# MicroMouse.net
KiCad netlist of a schematic drawn in Altium Designer
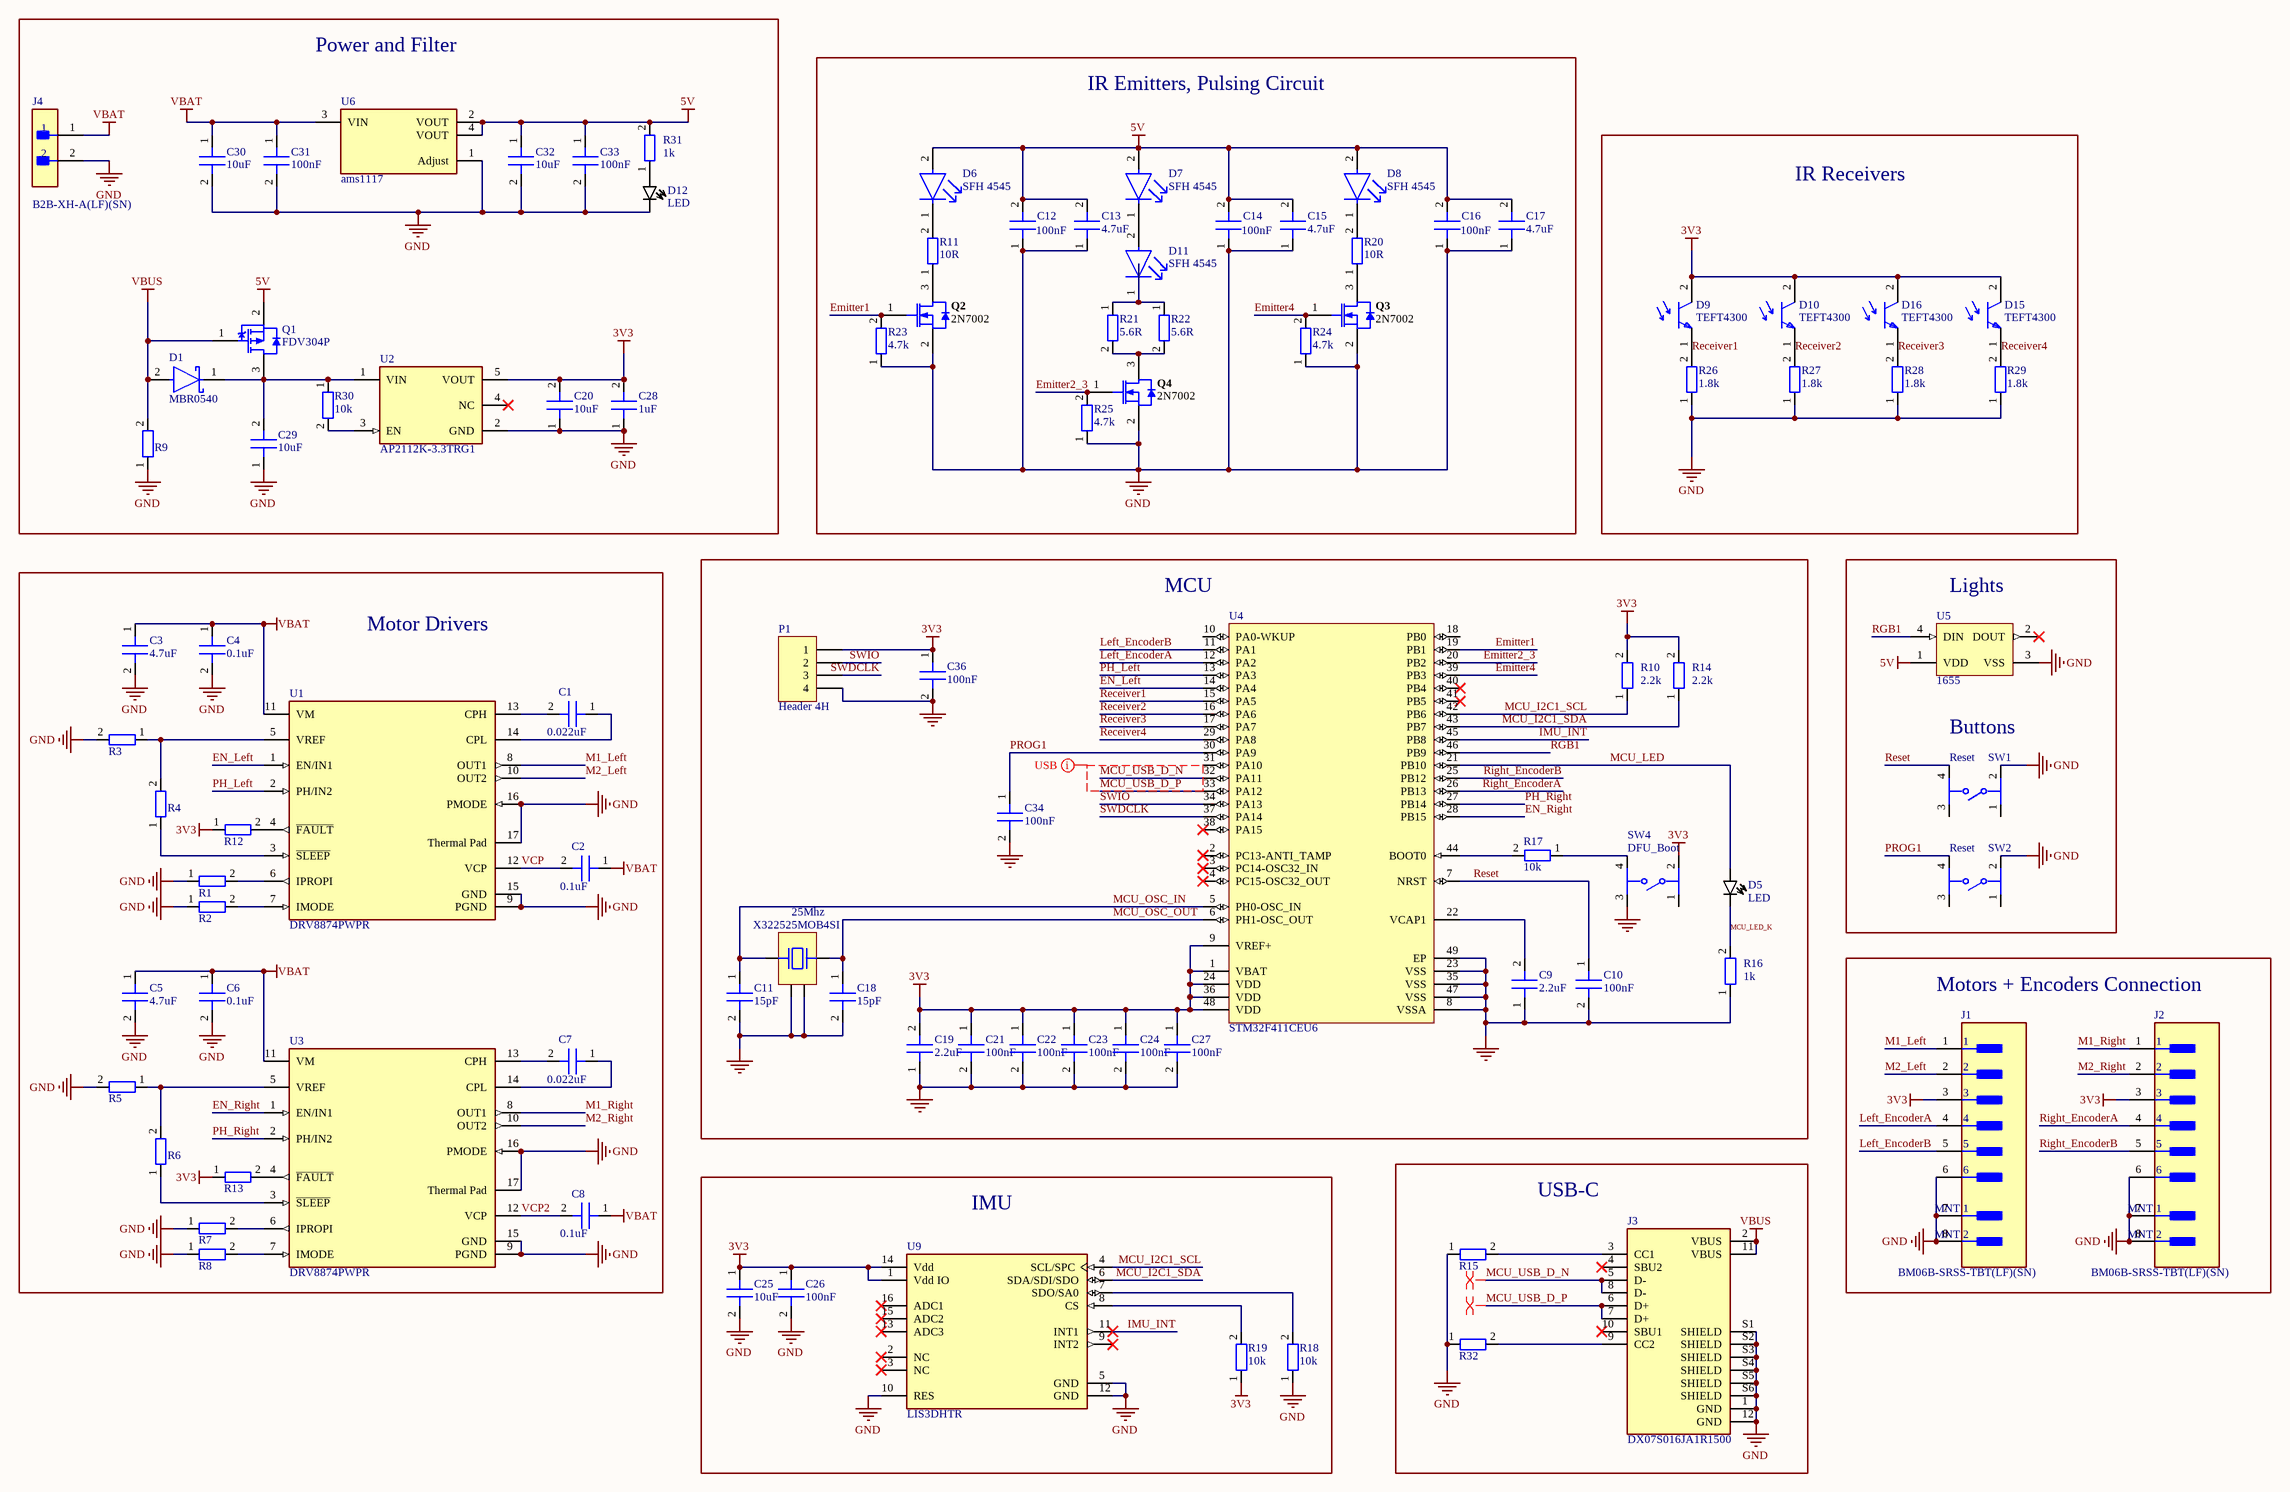
[diagram p0: MicroMouse.SchDoc]

(export (version "E")
  (design (tool "Eeschema 10.0.6"))
  (components
    (comp (ref "C1")
      (value "0.022uF")
      (footprint "IPC C C0603 No Silk")
      (libsource (lib "UBC AeroDesign") (part "CAP 0402 4.7uF CL05A475MP5NRNC"))
    )
    (comp (ref "C2")
      (value "0.1uF")
      (footprint "IPC C C0603 No Silk")
      (description "16V rated")
      (libsource (lib "UBC AeroDesign") (part "CAP 0402 4.7uF CL05A475MP5NRNC"))
    )
    (comp (ref "C3")
      (value "4.7uF")
      (footprint "IPC C C0603 No Silk")
      (libsource (lib "UBC AeroDesign") (part "CAP 0402 4.7uF CL05A475MP5NRNC"))
    )
    (comp (ref "C4")
      (value "0.1uF")
      (footprint "IPC C C0603 No Silk")
      (libsource (lib "UBC AeroDesign") (part "CAP 0402 4.7uF CL05A475MP5NRNC"))
    )
    (comp (ref "C5")
      (value "4.7uF")
      (footprint "IPC C C0603 No Silk")
      (libsource (lib "UBC AeroDesign") (part "CAP 0402 4.7uF CL05A475MP5NRNC"))
    )
    (comp (ref "C6")
      (value "0.1uF")
      (footprint "IPC C C0603 No Silk")
      (libsource (lib "UBC AeroDesign") (part "CAP 0402 4.7uF CL05A475MP5NRNC"))
    )
    (comp (ref "C7")
      (value "0.022uF")
      (footprint "IPC C C0603 No Silk")
      (libsource (lib "UBC AeroDesign") (part "CAP 0402 4.7uF CL05A475MP5NRNC"))
    )
    (comp (ref "C8")
      (value "0.1uF")
      (footprint "IPC C C0603 No Silk")
      (description "16V rated")
      (libsource (lib "UBC AeroDesign") (part "CAP 0402 4.7uF CL05A475MP5NRNC"))
    )
    (comp (ref "C9")
      (value "2.2uF")
      (footprint "IPC C C0603 No Silk")
      (libsource (lib "UBC AeroDesign") (part "CAP 0402 4.7uF CL05A475MP5NRNC"))
    )
    (comp (ref "C10")
      (value "100nF")
      (footprint "IPC C C0603 No Silk")
      (libsource (lib "UBC AeroDesign") (part "CAP 0402 4.7uF CL05A475MP5NRNC"))
    )
    (comp (ref "C11")
      (value "15pF")
      (footprint "IPC C C0603 No Silk")
      (libsource (lib "UBC AeroDesign") (part "CAP 0402 4.7uF CL05A475MP5NRNC"))
    )
    (comp (ref "C12")
      (value "100nF")
      (footprint "IPC C C0603 No Silk")
      (libsource (lib "UBC AeroDesign") (part "CAP 0402 4.7uF CL05A475MP5NRNC"))
    )
    (comp (ref "C13")
      (value "4.7uF")
      (footprint "IPC C C0603 No Silk")
      (libsource (lib "UBC AeroDesign") (part "CAP 0402 4.7uF CL05A475MP5NRNC"))
    )
    (comp (ref "C14")
      (value "100nF")
      (footprint "IPC C C0603 No Silk")
      (libsource (lib "UBC AeroDesign") (part "CAP 0402 4.7uF CL05A475MP5NRNC"))
    )
    (comp (ref "C15")
      (value "4.7uF")
      (footprint "IPC C C0603 No Silk")
      (libsource (lib "UBC AeroDesign") (part "CAP 0402 4.7uF CL05A475MP5NRNC"))
    )
    (comp (ref "C16")
      (value "100nF")
      (footprint "IPC C C0603 No Silk")
      (libsource (lib "UBC AeroDesign") (part "CAP 0402 4.7uF CL05A475MP5NRNC"))
    )
    (comp (ref "C17")
      (value "4.7uF")
      (footprint "IPC C C0603 No Silk")
      (libsource (lib "UBC AeroDesign") (part "CAP 0402 4.7uF CL05A475MP5NRNC"))
    )
    (comp (ref "C18")
      (value "15pF")
      (footprint "IPC C C0603 No Silk")
      (libsource (lib "UBC AeroDesign") (part "CAP 0402 4.7uF CL05A475MP5NRNC"))
    )
    (comp (ref "C19")
      (value "2.2uF")
      (footprint "IPC C C0603 No Silk")
      (libsource (lib "UBC AeroDesign") (part "CAP 0402 4.7uF CL05A475MP5NRNC"))
    )
    (comp (ref "C20")
      (value "10uF")
      (footprint "IPC C C0603 No Silk")
      (libsource (lib "UBC AeroDesign") (part "CAP 0402 4.7uF CL05A475MP5NRNC"))
    )
    (comp (ref "C21")
      (value "100nF")
      (footprint "IPC C C0603 No Silk")
      (libsource (lib "UBC AeroDesign") (part "CAP 0402 4.7uF CL05A475MP5NRNC"))
    )
    (comp (ref "C22")
      (value "100nF")
      (footprint "IPC C C0603 No Silk")
      (libsource (lib "UBC AeroDesign") (part "CAP 0402 4.7uF CL05A475MP5NRNC"))
    )
    (comp (ref "C23")
      (value "100nF")
      (footprint "IPC C C0603 No Silk")
      (libsource (lib "UBC AeroDesign") (part "CAP 0402 4.7uF CL05A475MP5NRNC"))
    )
    (comp (ref "C24")
      (value "100nF")
      (footprint "IPC C C0603 No Silk")
      (libsource (lib "UBC AeroDesign") (part "CAP 0402 4.7uF CL05A475MP5NRNC"))
    )
    (comp (ref "C25")
      (value "10uF")
      (footprint "IPC C C0603 No Silk")
      (libsource (lib "UBC AeroDesign") (part "CAP 0402 4.7uF CL05A475MP5NRNC"))
    )
    (comp (ref "C26")
      (value "100nF")
      (footprint "IPC C C0603 No Silk")
      (libsource (lib "UBC AeroDesign") (part "CAP 0402 4.7uF CL05A475MP5NRNC"))
    )
    (comp (ref "C27")
      (value "100nF")
      (footprint "IPC C C0603 No Silk")
      (libsource (lib "UBC AeroDesign") (part "CAP 0402 4.7uF CL05A475MP5NRNC"))
    )
    (comp (ref "C28")
      (value "1uF")
      (footprint "IPC C C0603 No Silk")
      (libsource (lib "UBC AeroDesign") (part "CAP 0402 4.7uF CL05A475MP5NRNC"))
    )
    (comp (ref "C29")
      (value "10uF")
      (footprint "IPC C C0603 No Silk")
      (libsource (lib "UBC AeroDesign") (part "CAP 0402 4.7uF CL05A475MP5NRNC"))
    )
    (comp (ref "C30")
      (value "10uF")
      (footprint "IPC C C0603 No Silk")
      (libsource (lib "UBC AeroDesign") (part "CAP 0402 4.7uF CL05A475MP5NRNC"))
    )
    (comp (ref "C31")
      (value "100nF")
      (footprint "IPC C C0603 No Silk")
      (libsource (lib "UBC AeroDesign") (part "CAP 0402 4.7uF CL05A475MP5NRNC"))
    )
    (comp (ref "C32")
      (value "10uF")
      (footprint "IPC C C0603 No Silk")
      (libsource (lib "UBC AeroDesign") (part "CAP 0402 4.7uF CL05A475MP5NRNC"))
    )
    (comp (ref "C33")
      (value "100nF")
      (footprint "IPC C C0603 No Silk")
      (libsource (lib "UBC AeroDesign") (part "CAP 0402 4.7uF CL05A475MP5NRNC"))
    )
    (comp (ref "C34")
      (value "100nF")
      (footprint "IPC C C0603 No Silk")
      (libsource (lib "UBC AeroDesign") (part "CAP 0402 4.7uF CL05A475MP5NRNC"))
    )
    (comp (ref "C36")
      (value "100nF")
      (footprint "IPC C C0603 No Silk")
      (libsource (lib "UBC AeroDesign") (part "CAP 0402 4.7uF CL05A475MP5NRNC"))
    )
    (comp (ref "D1")
      (value "MBR0540")
      (footprint "FP-425-04-MFG")
      (description "DIODE SCHOTTKY 40V 500MA SOD123")
      (libsource (lib "Altium Content Vault") (part "1d6ec82d83fb6aee721767c19dac4b9"))
    )
    (comp (ref "D5")
      (value "LED")
      (footprint "LED0603-FD_BLUE")
      (libsource (lib "UBC AeroDesign") (part "Generic LED 0603"))
    )
    (comp (ref "D6")
      (value "SFH 4545")
      (footprint "FP-SFH_4556-MFG")
      (description "EMITTER IR 860NM 100MA RADIAL")
      (fields
        (field (name "OCTOPART") "https://octopart.com/sfh+4556-osram+opto-31094094")
        (field (name "MANUFACTURER PART NUMBER") "SFH 4556")
      )
      (libsource (lib "Altium Content Vault") (part "8706943c75ba83719d021d2fdc84c58"))
    )
    (comp (ref "D7")
      (value "SFH 4545")
      (footprint "FP-SFH_4556-MFG")
      (description "EMITTER IR 860NM 100MA RADIAL")
      (fields
        (field (name "OCTOPART") "https://octopart.com/sfh+4556-osram+opto-31094094")
        (field (name "MANUFACTURER PART NUMBER") "SFH 4556")
      )
      (libsource (lib "Altium Content Vault") (part "8706943c75ba83719d021d2fdc84c58"))
    )
    (comp (ref "D8")
      (value "SFH 4545")
      (footprint "FP-SFH_4556-MFG")
      (description "EMITTER IR 860NM 100MA RADIAL")
      (fields
        (field (name "OCTOPART") "https://octopart.com/sfh+4556-osram+opto-31094094")
        (field (name "MANUFACTURER PART NUMBER") "SFH 4556")
      )
      (libsource (lib "Altium Content Vault") (part "8706943c75ba83719d021d2fdc84c58"))
    )
    (comp (ref "D9")
      (value "TEFT4300")
      (footprint "FP-6_544-5269_01-4-MFG")
      (description "TEFT4300 PHOTOTRANSISTOR 3.0MM WIDE VIEW / Phototransistor IR Chip Silicon 925nm 2-Pin T-1")
      (libsource (lib "Altium Content Vault") (part "fcf5d96e013ede1c9e051256f92411f"))
    )
    (comp (ref "D10")
      (value "TEFT4300")
      (footprint "FP-6_544-5269_01-4-MFG")
      (description "TEFT4300 PHOTOTRANSISTOR 3.0MM WIDE VIEW / Phototransistor IR Chip Silicon 925nm 2-Pin T-1")
      (libsource (lib "Altium Content Vault") (part "fcf5d96e013ede1c9e051256f92411f"))
    )
    (comp (ref "D11")
      (value "SFH 4545")
      (footprint "FP-SFH_4556-MFG")
      (description "EMITTER IR 860NM 100MA RADIAL")
      (fields
        (field (name "OCTOPART") "https://octopart.com/sfh+4556-osram+opto-31094094")
        (field (name "MANUFACTURER PART NUMBER") "SFH 4556")
      )
      (libsource (lib "Altium Content Vault") (part "8706943c75ba83719d021d2fdc84c58"))
    )
    (comp (ref "D12")
      (value "LED")
      (footprint "LED0603-FD_BLUE")
      (libsource (lib "UBC AeroDesign") (part "Generic LED 0603"))
    )
    (comp (ref "D15")
      (value "TEFT4300")
      (footprint "FP-6_544-5269_01-4-MFG")
      (description "TEFT4300 PHOTOTRANSISTOR 3.0MM WIDE VIEW / Phototransistor IR Chip Silicon 925nm 2-Pin T-1")
      (libsource (lib "Altium Content Vault") (part "fcf5d96e013ede1c9e051256f92411f"))
    )
    (comp (ref "D16")
      (value "TEFT4300")
      (footprint "FP-6_544-5269_01-4-MFG")
      (description "TEFT4300 PHOTOTRANSISTOR 3.0MM WIDE VIEW / Phototransistor IR Chip Silicon 925nm 2-Pin T-1")
      (libsource (lib "Altium Content Vault") (part "fcf5d96e013ede1c9e051256f92411f"))
    )
    (comp (ref "J1")
      (value "BM06B-SRSS-TBT(LF)(SN)")
      (footprint "FP-BM06B-SRSS-TBT_LF_SN-MFG")
      (description "CONN HEADER SMD 6POS 1MM")
      (libsource (lib "Altium Content Vault") (part "ed24c53d9ba001d1a2a686240a95171"))
    )
    (comp (ref "J2")
      (value "BM06B-SRSS-TBT(LF)(SN)")
      (footprint "FP-BM06B-SRSS-TBT_LF_SN-MFG")
      (description "CONN HEADER SMD 6POS 1MM")
      (libsource (lib "Altium Content Vault") (part "ed24c53d9ba001d1a2a686240a95171"))
    )
    (comp (ref "J3")
      (value "DX07S016JA1R1500")
      (footprint "JAE_DX07S016JA1R1500")
      (libsource (lib "UBC AeroDesign") (part "DX07S016JA1R1500"))
    )
    (comp (ref "J4")
      (value "B2B-XH-A(LF)(SN)")
      (footprint "FP-B2B-XH-A_LF_SN-MFG")
      (description "CONN HEADER VERT 2POS 2.5MM")
      (libsource (lib "Altium Content Vault") (part "3bc925449376181038e59eaffc5286c"))
    )
    (comp (ref "P1")
      (value "Header 4H")
      (footprint "HDR1X4H")
      (description "Header, 4-Pin, Right Angle")
      (fields (field (name "PUBLISHER") "Altium Limited"))
      (libsource (lib "UBC AeroDesign") (part "Header 4H"))
    )
    (comp (ref "Q1")
      (value "FDV304P")
      (footprint "FAIR-SOT23-3_V")
      (fields (field (name "MANUFACTURER") "FairchildSemiconductor"))
      (libsource (lib "Altium Content Vault") (part "PEMOS-GSD-3_B"))
    )
    (comp (ref "Q2")
      (value "2N7002")
      (footprint "INF-PG-SOT23_M")
      (fields (field (name "MANUFACTURER") "Infineon"))
      (libsource (lib "Altium Content Vault") (part "INF-NDMOS-GSD-3"))
    )
    (comp (ref "Q3")
      (value "2N7002")
      (footprint "INF-PG-SOT23_M")
      (fields (field (name "MANUFACTURER") "Infineon"))
      (libsource (lib "Altium Content Vault") (part "INF-NDMOS-GSD-3"))
    )
    (comp (ref "Q4")
      (value "2N7002")
      (footprint "INF-PG-SOT23_M")
      (fields (field (name "MANUFACTURER") "Infineon"))
      (libsource (lib "Altium Content Vault") (part "INF-NDMOS-GSD-3"))
    )
    (comp (ref "R1")
      (value "2.49k")
      (footprint "IPC C R0603 No Silk")
      (libsource (lib "UBC AeroDesign") (part "RES 0402 5.1k 0402WGF5101TCE"))
    )
    (comp (ref "R2")
      (value "20k")
      (footprint "IPC C R0603 No Silk")
      (libsource (lib "UBC AeroDesign") (part "RES 0402 5.1k 0402WGF5101TCE"))
    )
    (comp (ref "R3")
      (value "0")
      (footprint "IPC C R0603 No Silk")
      (libsource (lib "UBC AeroDesign") (part "RES 0402 5.1k 0402WGF5101TCE"))
    )
    (comp (ref "R4")
      (value "10k")
      (footprint "IPC C R0603 No Silk")
      (libsource (lib "UBC AeroDesign") (part "RES 0402 5.1k 0402WGF5101TCE"))
    )
    (comp (ref "R5")
      (value "0")
      (footprint "IPC C R0603 No Silk")
      (libsource (lib "UBC AeroDesign") (part "RES 0402 5.1k 0402WGF5101TCE"))
    )
    (comp (ref "R6")
      (value "10k")
      (footprint "IPC C R0603 No Silk")
      (libsource (lib "UBC AeroDesign") (part "RES 0402 5.1k 0402WGF5101TCE"))
    )
    (comp (ref "R7")
      (value "2.49k")
      (footprint "IPC C R0603 No Silk")
      (libsource (lib "UBC AeroDesign") (part "RES 0402 5.1k 0402WGF5101TCE"))
    )
    (comp (ref "R8")
      (value "20k")
      (footprint "IPC C R0603 No Silk")
      (libsource (lib "UBC AeroDesign") (part "RES 0402 5.1k 0402WGF5101TCE"))
    )
    (comp (ref "R9")
      (value "100k")
      (footprint "IPC C R0603 No Silk")
      (libsource (lib "UBC AeroDesign") (part "RES 0402 5.1k 0402WGF5101TCE"))
    )
    (comp (ref "R10")
      (value "2.2k")
      (footprint "IPC C R0603 No Silk")
      (libsource (lib "UBC AeroDesign") (part "RES 0402 5.1k 0402WGF5101TCE"))
    )
    (comp (ref "R11")
      (value "10R")
      (footprint "IPC C R0603 No Silk")
      (libsource (lib "UBC AeroDesign") (part "RES 0402 5.1k 0402WGF5101TCE"))
    )
    (comp (ref "R12")
      (value "10k")
      (footprint "IPC C R0603 No Silk")
      (libsource (lib "UBC AeroDesign") (part "RES 0402 5.1k 0402WGF5101TCE"))
    )
    (comp (ref "R13")
      (value "10k")
      (footprint "IPC C R0603 No Silk")
      (libsource (lib "UBC AeroDesign") (part "RES 0402 5.1k 0402WGF5101TCE"))
    )
    (comp (ref "R14")
      (value "2.2k")
      (footprint "IPC C R0603 No Silk")
      (libsource (lib "UBC AeroDesign") (part "RES 0402 5.1k 0402WGF5101TCE"))
    )
    (comp (ref "R15")
      (value "Generic RES 0603")
      (footprint "IPC C R0603 No Silk")
      (libsource (lib "UBC AeroDesign") (part "RES 0402 5.1k 0402WGF5101TCE"))
    )
    (comp (ref "R16")
      (value "1k")
      (footprint "IPC C R0603 No Silk")
      (libsource (lib "UBC AeroDesign") (part "RES 0402 5.1k 0402WGF5101TCE"))
    )
    (comp (ref "R17")
      (value "10k")
      (footprint "IPC C R0603 No Silk")
      (libsource (lib "UBC AeroDesign") (part "RES 0402 5.1k 0402WGF5101TCE"))
    )
    (comp (ref "R18")
      (value "10k")
      (footprint "IPC C R0603 No Silk")
      (libsource (lib "UBC AeroDesign") (part "RES 0402 5.1k 0402WGF5101TCE"))
    )
    (comp (ref "R19")
      (value "10k")
      (footprint "IPC C R0603 No Silk")
      (libsource (lib "UBC AeroDesign") (part "RES 0402 5.1k 0402WGF5101TCE"))
    )
    (comp (ref "R20")
      (value "10R")
      (footprint "IPC C R0603 No Silk")
      (libsource (lib "UBC AeroDesign") (part "RES 0402 5.1k 0402WGF5101TCE"))
    )
    (comp (ref "R21")
      (value "5.6R")
      (footprint "IPC C R0603 No Silk")
      (libsource (lib "UBC AeroDesign") (part "RES 0402 5.1k 0402WGF5101TCE"))
    )
    (comp (ref "R22")
      (value "5.6R")
      (footprint "IPC C R0603 No Silk")
      (libsource (lib "UBC AeroDesign") (part "RES 0402 5.1k 0402WGF5101TCE"))
    )
    (comp (ref "R23")
      (value "4.7k")
      (footprint "IPC C R0603 No Silk")
      (libsource (lib "UBC AeroDesign") (part "RES 0402 5.1k 0402WGF5101TCE"))
    )
    (comp (ref "R24")
      (value "4.7k")
      (footprint "IPC C R0603 No Silk")
      (libsource (lib "UBC AeroDesign") (part "RES 0402 5.1k 0402WGF5101TCE"))
    )
    (comp (ref "R25")
      (value "4.7k")
      (footprint "IPC C R0603 No Silk")
      (libsource (lib "UBC AeroDesign") (part "RES 0402 5.1k 0402WGF5101TCE"))
    )
    (comp (ref "R26")
      (value "1.8k")
      (footprint "IPC C R0603 No Silk")
      (libsource (lib "UBC AeroDesign") (part "RES 0402 5.1k 0402WGF5101TCE"))
    )
    (comp (ref "R27")
      (value "1.8k")
      (footprint "IPC C R0603 No Silk")
      (libsource (lib "UBC AeroDesign") (part "RES 0402 5.1k 0402WGF5101TCE"))
    )
    (comp (ref "R28")
      (value "1.8k")
      (footprint "IPC C R0603 No Silk")
      (libsource (lib "UBC AeroDesign") (part "RES 0402 5.1k 0402WGF5101TCE"))
    )
    (comp (ref "R29")
      (value "1.8k")
      (footprint "IPC C R0603 No Silk")
      (libsource (lib "UBC AeroDesign") (part "RES 0402 5.1k 0402WGF5101TCE"))
    )
    (comp (ref "R30")
      (value "10k")
      (footprint "IPC C R0603 No Silk")
      (libsource (lib "UBC AeroDesign") (part "RES 0402 5.1k 0402WGF5101TCE"))
    )
    (comp (ref "R31")
      (value "1k")
      (footprint "IPC C R0603 No Silk")
      (libsource (lib "UBC AeroDesign") (part "RES 0402 5.1k 0402WGF5101TCE"))
    )
    (comp (ref "R32")
      (value "Generic RES 0603")
      (footprint "IPC C R0603 No Silk")
      (libsource (lib "UBC AeroDesign") (part "RES 0402 5.1k 0402WGF5101TCE"))
    )
    (comp (ref "SW1")
      (value "Reset")
      (footprint "FP-PTS526SK15SMTR2LFS-MFG")
      (description "TACT 5.2 X 5.2, 1.5 MM H, 260GF,")
      (fields
        (field (name "MANUFACTURER") "C&K")
        (field (name "MANUFACTURER PART NUMBER") "PTS526SK15SMTR2LFS")
      )
      (libsource (lib "Altium Content Vault") (part "b8895f3f4cefb76e1819d2863dba89b"))
    )
    (comp (ref "SW2")
      (value "Reset")
      (footprint "FP-PTS526SK15SMTR2LFS-MFG")
      (description "TACT 5.2 X 5.2, 1.5 MM H, 260GF,")
      (fields
        (field (name "MANUFACTURER") "C&K")
        (field (name "MANUFACTURER PART NUMBER") "PTS526SK15SMTR2LFS")
      )
      (libsource (lib "Altium Content Vault") (part "b8895f3f4cefb76e1819d2863dba89b"))
    )
    (comp (ref "SW4")
      (value "DFU_Boot")
      (footprint "FP-PTS526SK15SMTR2LFS-MFG")
      (description "TACT 5.2 X 5.2, 1.5 MM H, 260GF,")
      (fields
        (field (name "MANUFACTURER") "C&K")
        (field (name "MANUFACTURER PART NUMBER") "PTS526SK15SMTR2LFS")
      )
      (libsource (lib "Altium Content Vault") (part "b8895f3f4cefb76e1819d2863dba89b"))
    )
    (comp (ref "U1")
      (value "DRV8874PWPR")
      (footprint "FP-PWP0016J-MFG")
      (description "DRV8874 H-BRIDGE MOTOR DRIVER")
      (libsource (lib "Altium Content Vault") (part "a5fc859173bb0b9b9cdb17a7cc0dfbc"))
    )
    (comp (ref "U2")
      (value "AP2112K-3.3TRG1")
      (footprint "FP-SOT25-IPC_A")
      (description "IC REG LINEAR 3.3V 600MA SOT25")
      (libsource (lib "Altium Content Vault") (part "c8ab751aee5229183125ab046a11caa"))
    )
    (comp (ref "U3")
      (value "DRV8874PWPR")
      (footprint "FP-PWP0016J-MFG")
      (description "DRV8874 H-BRIDGE MOTOR DRIVER")
      (libsource (lib "Altium Content Vault") (part "a5fc859173bb0b9b9cdb17a7cc0dfbc"))
    )
    (comp (ref "U4")
      (value "STM32F411CEU6")
      (footprint "STM-UFQFPN48_L")
      (libsource (lib "Altium Content Vault") (part "MC-ARM-STM32F411-UFQFPN48"))
    )
    (comp (ref "U5")
      (value "1655")
      (footprint "ADA-RGB-1655_V")
      (fields (field (name "MANUFACTURER") "Adafruit-Industries-LLC"))
      (libsource (lib "Altium Content Vault") (part "ADA-RGB-1655-4"))
    )
    (comp (ref "U6")
      (value "ams1117")
      (footprint "FP-ams1117-IPC_C")
      (description "1A LOW DROPOUT VOLTAGE REGULATOR")
      (libsource (lib "Altium Content Vault") (part "59ad430b93a2c51b3e6ee7c3b069677"))
    )
    (comp (ref "U9")
      (value "LIS3DHTR")
      (footprint "FP-LGA-16-7983231-MFG")
      (description "ACCEL 2-16G I2C/SPI 16LGA")
      (libsource (lib "Altium Content Vault") (part "1e4772b22d749da4b53766bc623c8dd"))
    )
    (comp (ref "X322525MOB4SI")
      (value "25Mhz")
      (footprint "OSC-SMD_4P-L3.2-W2.5-BL")
      (fields (field (name "MANUFACTURER") "YXC(扬兴晶振)") (field (name "MANUFACTURER PART") "X322525MOB4SI"))
      (libsource (lib "JLCPCB Library") (part "Crystal 25MHz X322525MOB4SI"))
    )
  )
  (nets
    (net (code "1") (name "/EN_Left") (class "Default")
      (node (ref "U1") (pin "1") (pinfunction "EN/IN1_1") (pintype "input"))
      (node (ref "U4") (pin "14") (pinfunction "PA4_14") (pintype "bidirectional"))
    )
    (net (code "2") (name "/EN_Right") (class "Default")
      (node (ref "U3") (pin "1") (pinfunction "EN/IN1_1") (pintype "input"))
      (node (ref "U4") (pin "28") (pinfunction "PB15_28") (pintype "bidirectional"))
    )
    (net (code "3") (name "/Emitter1") (class "Default")
      (node (ref "Q2") (pin "1") (pinfunction "GATE_1") (pintype "passive"))
      (node (ref "R23") (pin "2") (pinfunction "2_2") (pintype "passive"))
      (node (ref "U4") (pin "19") (pinfunction "PB1_19") (pintype "bidirectional"))
    )
    (net (code "4") (name "/Emitter2_3") (class "Default")
      (node (ref "Q4") (pin "1") (pinfunction "GATE_1") (pintype "passive"))
      (node (ref "R25") (pin "2") (pinfunction "2_2") (pintype "passive"))
      (node (ref "U4") (pin "20") (pinfunction "PB2_20") (pintype "bidirectional"))
    )
    (net (code "5") (name "/Emitter4") (class "Default")
      (node (ref "Q3") (pin "1") (pinfunction "GATE_1") (pintype "passive"))
      (node (ref "R24") (pin "2") (pinfunction "2_2") (pintype "passive"))
      (node (ref "U4") (pin "39") (pinfunction "PB3_39") (pintype "bidirectional"))
    )
    (net (code "6") (name "/IMU_INT") (class "Default")
      (node (ref "U4") (pin "45") (pinfunction "PB8_45") (pintype "bidirectional"))
      (node (ref "U9") (pin "11") (pinfunction "INT1_11") (pintype "output"))
    )
    (net (code "7") (name "/Left_EncoderA") (class "Default")
      (node (ref "J1") (pin "4") (pinfunction "4_4") (pintype "passive"))
      (node (ref "U4") (pin "12") (pinfunction "PA2_12") (pintype "bidirectional"))
    )
    (net (code "8") (name "/Left_EncoderB") (class "Default")
      (node (ref "J1") (pin "5") (pinfunction "5_5") (pintype "passive"))
      (node (ref "U4") (pin "11") (pinfunction "PA1_11") (pintype "bidirectional"))
    )
    (net (code "9") (name "/M1_Left") (class "Default")
      (node (ref "J1") (pin "1") (pinfunction "1_1") (pintype "passive"))
      (node (ref "U1") (pin "8") (pinfunction "OUT1_8") (pintype "output"))
    )
    (net (code "10") (name "/M1_Right") (class "Default")
      (node (ref "J2") (pin "1") (pinfunction "1_1") (pintype "passive"))
      (node (ref "U3") (pin "8") (pinfunction "OUT1_8") (pintype "output"))
    )
    (net (code "11") (name "/M2_Left") (class "Default")
      (node (ref "J1") (pin "2") (pinfunction "2_2") (pintype "passive"))
      (node (ref "U1") (pin "10") (pinfunction "OUT2_10") (pintype "output"))
    )
    (net (code "12") (name "/M2_Right") (class "Default")
      (node (ref "J2") (pin "2") (pinfunction "2_2") (pintype "passive"))
      (node (ref "U3") (pin "10") (pinfunction "OUT2_10") (pintype "output"))
    )
    (net (code "13") (name "/MCU_I2C1_SCL") (class "Default")
      (node (ref "R10") (pin "1") (pinfunction "1_1") (pintype "passive"))
      (node (ref "U4") (pin "42") (pinfunction "PB6_42") (pintype "bidirectional"))
      (node (ref "U9") (pin "4") (pinfunction "SCL/SPC_4") (pintype "input"))
    )
    (net (code "14") (name "/MCU_I2C1_SDA") (class "Default")
      (node (ref "R14") (pin "1") (pinfunction "1_1") (pintype "passive"))
      (node (ref "U4") (pin "43") (pinfunction "PB7_43") (pintype "bidirectional"))
      (node (ref "U9") (pin "6") (pinfunction "SDA/SDI/SDO_6") (pintype "bidirectional"))
    )
    (net (code "15") (name "/MCU_LED") (class "Default")
      (node (ref "D5") (pin "1") (pinfunction "A_1") (pintype "passive"))
      (node (ref "U4") (pin "21") (pinfunction "PB10_21") (pintype "bidirectional"))
    )
    (net (code "16") (name "/MCU_LED_K") (class "Default")
      (node (ref "D5") (pin "2") (pinfunction "C_2") (pintype "passive"))
      (node (ref "R16") (pin "2") (pinfunction "2_2") (pintype "passive"))
    )
    (net (code "17") (name "/MCU_OSC_IN") (class "Default")
      (node (ref "C11") (pin "1") (pinfunction "1_1") (pintype "passive"))
      (node (ref "U4") (pin "5") (pinfunction "PH0-OSC_IN_5") (pintype "bidirectional"))
      (node (ref "X322525MOB4SI") (pin "1") (pinfunction "1_1") (pintype "passive"))
    )
    (net (code "18") (name "/MCU_OSC_OUT") (class "Default")
      (node (ref "C18") (pin "1") (pinfunction "1_1") (pintype "passive"))
      (node (ref "U4") (pin "6") (pinfunction "PH1-OSC_OUT_6") (pintype "bidirectional"))
      (node (ref "X322525MOB4SI") (pin "3") (pinfunction "3_3") (pintype "passive"))
    )
    (net (code "19") (name "/MCU_USB_D_N") (class "Default")
      (node (ref "J3") (pin "5") (pinfunction "D-_5") (pintype "passive"))
      (node (ref "J3") (pin "8") (pinfunction "D-_8") (pintype "passive"))
      (node (ref "U4") (pin "32") (pinfunction "PA11_32") (pintype "bidirectional"))
    )
    (net (code "20") (name "/MCU_USB_D_P") (class "Default")
      (node (ref "J3") (pin "6") (pinfunction "D+_6") (pintype "passive"))
      (node (ref "J3") (pin "7") (pinfunction "D+_7") (pintype "passive"))
      (node (ref "U4") (pin "33") (pinfunction "PA12_33") (pintype "bidirectional"))
    )
    (net (code "21") (name "/PH_Left") (class "Default")
      (node (ref "U1") (pin "2") (pinfunction "PH/IN2_2") (pintype "input"))
      (node (ref "U4") (pin "13") (pinfunction "PA3_13") (pintype "bidirectional"))
    )
    (net (code "22") (name "/PH_Right") (class "Default")
      (node (ref "U3") (pin "2") (pinfunction "PH/IN2_2") (pintype "input"))
      (node (ref "U4") (pin "27") (pinfunction "PB14_27") (pintype "bidirectional"))
    )
    (net (code "23") (name "/PROG1") (class "Default")
      (node (ref "C34") (pin "1") (pinfunction "1_1") (pintype "passive"))
      (node (ref "SW2") (pin "4") (pinfunction "4_4") (pintype "passive"))
      (node (ref "U4") (pin "30") (pinfunction "PA9_30") (pintype "bidirectional"))
    )
    (net (code "24") (name "/RGB1") (class "Default")
      (node (ref "U4") (pin "46") (pinfunction "PB9_46") (pintype "bidirectional"))
      (node (ref "U5") (pin "4") (pinfunction "DIN_4") (pintype "input"))
    )
    (net (code "25") (name "/Receiver1") (class "Default")
      (node (ref "D9") (pin "1") (pinfunction "E_1") (pintype "passive"))
      (node (ref "R26") (pin "2") (pinfunction "2_2") (pintype "passive"))
      (node (ref "U4") (pin "15") (pinfunction "PA5_15") (pintype "bidirectional"))
    )
    (net (code "26") (name "/Receiver2") (class "Default")
      (node (ref "D10") (pin "1") (pinfunction "E_1") (pintype "passive"))
      (node (ref "R27") (pin "2") (pinfunction "2_2") (pintype "passive"))
      (node (ref "U4") (pin "16") (pinfunction "PA6_16") (pintype "bidirectional"))
    )
    (net (code "27") (name "/Receiver3") (class "Default")
      (node (ref "D16") (pin "1") (pinfunction "E_1") (pintype "passive"))
      (node (ref "R28") (pin "2") (pinfunction "2_2") (pintype "passive"))
      (node (ref "U4") (pin "17") (pinfunction "PA7_17") (pintype "bidirectional"))
    )
    (net (code "28") (name "/Receiver4") (class "Default")
      (node (ref "D15") (pin "1") (pinfunction "E_1") (pintype "passive"))
      (node (ref "R29") (pin "2") (pinfunction "2_2") (pintype "passive"))
      (node (ref "U4") (pin "29") (pinfunction "PA8_29") (pintype "bidirectional"))
    )
    (net (code "29") (name "/Reset") (class "Default")
      (node (ref "C10") (pin "1") (pinfunction "1_1") (pintype "passive"))
      (node (ref "SW1") (pin "4") (pinfunction "4_4") (pintype "passive"))
      (node (ref "U4") (pin "7") (pinfunction "NRST_7") (pintype "bidirectional"))
    )
    (net (code "30") (name "/Right_EncoderA") (class "Default")
      (node (ref "J2") (pin "4") (pinfunction "4_4") (pintype "passive"))
      (node (ref "U4") (pin "26") (pinfunction "PB13_26") (pintype "bidirectional"))
    )
    (net (code "31") (name "/Right_EncoderB") (class "Default")
      (node (ref "J2") (pin "5") (pinfunction "5_5") (pintype "passive"))
      (node (ref "U4") (pin "25") (pinfunction "PB12_25") (pintype "bidirectional"))
    )
    (net (code "32") (name "/SWDCLK") (class "Default")
      (node (ref "P1") (pin "3") (pinfunction "3_3") (pintype "passive"))
      (node (ref "U4") (pin "37") (pinfunction "PA14_37") (pintype "bidirectional"))
    )
    (net (code "33") (name "/SWIO") (class "Default")
      (node (ref "P1") (pin "2") (pinfunction "2_2") (pintype "passive"))
      (node (ref "U4") (pin "34") (pinfunction "PA13_34") (pintype "bidirectional"))
    )
    (net (code "34") (name "/VCP") (class "Default")
      (node (ref "C2") (pin "2") (pinfunction "2_2") (pintype "passive"))
      (node (ref "U1") (pin "12") (pinfunction "VCP_12") (pintype "power_in"))
    )
    (net (code "35") (name "/VCP2") (class "Default")
      (node (ref "C8") (pin "2") (pinfunction "2_2") (pintype "passive"))
      (node (ref "U3") (pin "12") (pinfunction "VCP_12") (pintype "power_in"))
    )
    (net (code "36") (name "3V3") (class "Default")
      (node (ref "C19") (pin "2") (pinfunction "2_2") (pintype "passive"))
      (node (ref "C20") (pin "2") (pinfunction "2_2") (pintype "passive"))
      (node (ref "C21") (pin "1") (pinfunction "1_1") (pintype "passive"))
      (node (ref "C22") (pin "1") (pinfunction "1_1") (pintype "passive"))
      (node (ref "C23") (pin "1") (pinfunction "1_1") (pintype "passive"))
      (node (ref "C24") (pin "1") (pinfunction "1_1") (pintype "passive"))
      (node (ref "C25") (pin "1") (pinfunction "1_1") (pintype "passive"))
      (node (ref "C26") (pin "1") (pinfunction "1_1") (pintype "passive"))
      (node (ref "C27") (pin "1") (pinfunction "1_1") (pintype "passive"))
      (node (ref "C28") (pin "2") (pinfunction "2_2") (pintype "passive"))
      (node (ref "C36") (pin "1") (pinfunction "1_1") (pintype "passive"))
      (node (ref "D10") (pin "2") (pinfunction "C_2") (pintype "passive"))
      (node (ref "D15") (pin "2") (pinfunction "C_2") (pintype "passive"))
      (node (ref "D16") (pin "2") (pinfunction "C_2") (pintype "passive"))
      (node (ref "D9") (pin "2") (pinfunction "C_2") (pintype "passive"))
      (node (ref "J1") (pin "3") (pinfunction "3_3") (pintype "passive"))
      (node (ref "J2") (pin "3") (pinfunction "3_3") (pintype "passive"))
      (node (ref "P1") (pin "1") (pinfunction "1_1") (pintype "passive"))
      (node (ref "R10") (pin "2") (pinfunction "2_2") (pintype "passive"))
      (node (ref "R12") (pin "1") (pinfunction "1_1") (pintype "passive"))
      (node (ref "R13") (pin "1") (pinfunction "1_1") (pintype "passive"))
      (node (ref "R14") (pin "2") (pinfunction "2_2") (pintype "passive"))
      (node (ref "R19") (pin "1") (pinfunction "1_1") (pintype "passive"))
      (node (ref "SW4") (pin "2") (pinfunction "2_2") (pintype "passive"))
      (node (ref "U2") (pin "5") (pinfunction "VOUT_5") (pintype "power_in"))
      (node (ref "U4") (pin "1") (pinfunction "VBAT_1") (pintype "power_in"))
      (node (ref "U4") (pin "24") (pinfunction "VDD_24") (pintype "power_in"))
      (node (ref "U4") (pin "36") (pinfunction "VDD_36") (pintype "power_in"))
      (node (ref "U4") (pin "48") (pinfunction "VDD_48") (pintype "power_in"))
      (node (ref "U4") (pin "9") (pinfunction "VREF+_9") (pintype "power_in"))
      (node (ref "U9") (pin "1") (pinfunction "Vdd_IO_1") (pintype "power_in"))
      (node (ref "U9") (pin "14") (pinfunction "Vdd_14") (pintype "power_in"))
    )
    (net (code "37") (name "5V") (class "Default")
      (node (ref "C12") (pin "2") (pinfunction "2_2") (pintype "passive"))
      (node (ref "C13") (pin "2") (pinfunction "2_2") (pintype "passive"))
      (node (ref "C14") (pin "2") (pinfunction "2_2") (pintype "passive"))
      (node (ref "C15") (pin "2") (pinfunction "2_2") (pintype "passive"))
      (node (ref "C16") (pin "2") (pinfunction "2_2") (pintype "passive"))
      (node (ref "C17") (pin "2") (pinfunction "2_2") (pintype "passive"))
      (node (ref "C32") (pin "1") (pinfunction "1_1") (pintype "passive"))
      (node (ref "C33") (pin "1") (pinfunction "1_1") (pintype "passive"))
      (node (ref "D6") (pin "2") (pinfunction "A_2") (pintype "passive"))
      (node (ref "D7") (pin "2") (pinfunction "A_2") (pintype "passive"))
      (node (ref "D8") (pin "2") (pinfunction "A_2") (pintype "passive"))
      (node (ref "Q1") (pin "2") (pinfunction "S_2") (pintype "passive"))
      (node (ref "R31") (pin "2") (pinfunction "2_2") (pintype "passive"))
      (node (ref "U5") (pin "1") (pinfunction "VDD_1") (pintype "power_in"))
      (node (ref "U6") (pin "2") (pinfunction "VOUT_2") (pintype "passive"))
      (node (ref "U6") (pin "4") (pinfunction "VOUT_4") (pintype "passive"))
    )
    (net (code "38") (name "GND") (class "Default")
      (node (ref "C10") (pin "2") (pinfunction "2_2") (pintype "passive"))
      (node (ref "C11") (pin "2") (pinfunction "2_2") (pintype "passive"))
      (node (ref "C12") (pin "1") (pinfunction "1_1") (pintype "passive"))
      (node (ref "C13") (pin "1") (pinfunction "1_1") (pintype "passive"))
      (node (ref "C14") (pin "1") (pinfunction "1_1") (pintype "passive"))
      (node (ref "C15") (pin "1") (pinfunction "1_1") (pintype "passive"))
      (node (ref "C16") (pin "1") (pinfunction "1_1") (pintype "passive"))
      (node (ref "C17") (pin "1") (pinfunction "1_1") (pintype "passive"))
      (node (ref "C18") (pin "2") (pinfunction "2_2") (pintype "passive"))
      (node (ref "C19") (pin "1") (pinfunction "1_1") (pintype "passive"))
      (node (ref "C20") (pin "1") (pinfunction "1_1") (pintype "passive"))
      (node (ref "C21") (pin "2") (pinfunction "2_2") (pintype "passive"))
      (node (ref "C22") (pin "2") (pinfunction "2_2") (pintype "passive"))
      (node (ref "C23") (pin "2") (pinfunction "2_2") (pintype "passive"))
      (node (ref "C24") (pin "2") (pinfunction "2_2") (pintype "passive"))
      (node (ref "C25") (pin "2") (pinfunction "2_2") (pintype "passive"))
      (node (ref "C26") (pin "2") (pinfunction "2_2") (pintype "passive"))
      (node (ref "C27") (pin "2") (pinfunction "2_2") (pintype "passive"))
      (node (ref "C28") (pin "1") (pinfunction "1_1") (pintype "passive"))
      (node (ref "C29") (pin "1") (pinfunction "1_1") (pintype "passive"))
      (node (ref "C3") (pin "2") (pinfunction "2_2") (pintype "passive"))
      (node (ref "C30") (pin "2") (pinfunction "2_2") (pintype "passive"))
      (node (ref "C31") (pin "2") (pinfunction "2_2") (pintype "passive"))
      (node (ref "C32") (pin "2") (pinfunction "2_2") (pintype "passive"))
      (node (ref "C33") (pin "2") (pinfunction "2_2") (pintype "passive"))
      (node (ref "C34") (pin "2") (pinfunction "2_2") (pintype "passive"))
      (node (ref "C36") (pin "2") (pinfunction "2_2") (pintype "passive"))
      (node (ref "C4") (pin "2") (pinfunction "2_2") (pintype "passive"))
      (node (ref "C5") (pin "2") (pinfunction "2_2") (pintype "passive"))
      (node (ref "C6") (pin "2") (pinfunction "2_2") (pintype "passive"))
      (node (ref "C9") (pin "1") (pinfunction "1_1") (pintype "passive"))
      (node (ref "D12") (pin "2") (pinfunction "C_2") (pintype "passive"))
      (node (ref "J1") (pin "6") (pinfunction "6_6") (pintype "passive"))
      (node (ref "J1") (pin "7") (pinfunction "MNT_1_7") (pintype "passive"))
      (node (ref "J1") (pin "8") (pinfunction "MNT_2_8") (pintype "passive"))
      (node (ref "J2") (pin "6") (pinfunction "6_6") (pintype "passive"))
      (node (ref "J2") (pin "7") (pinfunction "MNT_1_7") (pintype "passive"))
      (node (ref "J2") (pin "8") (pinfunction "MNT_2_8") (pintype "passive"))
      (node (ref "J3") (pin "1") (pinfunction "GND_1") (pintype "power_in"))
      (node (ref "J3") (pin "12") (pinfunction "GND_12") (pintype "power_in"))
      (node (ref "J3") (pin "S1") (pinfunction "SHIELD_S1") (pintype "passive"))
      (node (ref "J3") (pin "S2") (pinfunction "SHIELD_S2") (pintype "passive"))
      (node (ref "J3") (pin "S3") (pinfunction "SHIELD_S3") (pintype "passive"))
      (node (ref "J3") (pin "S4") (pinfunction "SHIELD_S4") (pintype "passive"))
      (node (ref "J3") (pin "S5") (pinfunction "SHIELD_S5") (pintype "passive"))
      (node (ref "J3") (pin "S6") (pinfunction "SHIELD_S6") (pintype "passive"))
      (node (ref "J4") (pin "2") (pinfunction "2_2") (pintype "passive"))
      (node (ref "P1") (pin "4") (pinfunction "4_4") (pintype "passive"))
      (node (ref "Q2") (pin "2") (pinfunction "SOURCE_2") (pintype "passive"))
      (node (ref "Q3") (pin "2") (pinfunction "SOURCE_2") (pintype "passive"))
      (node (ref "Q4") (pin "2") (pinfunction "SOURCE_2") (pintype "passive"))
      (node (ref "R1") (pin "1") (pinfunction "1_1") (pintype "passive"))
      (node (ref "R15") (pin "1") (pinfunction "1_1") (pintype "passive"))
      (node (ref "R16") (pin "1") (pinfunction "1_1") (pintype "passive"))
      (node (ref "R18") (pin "1") (pinfunction "1_1") (pintype "passive"))
      (node (ref "R2") (pin "1") (pinfunction "1_1") (pintype "passive"))
      (node (ref "R23") (pin "1") (pinfunction "1_1") (pintype "passive"))
      (node (ref "R24") (pin "1") (pinfunction "1_1") (pintype "passive"))
      (node (ref "R25") (pin "1") (pinfunction "1_1") (pintype "passive"))
      (node (ref "R26") (pin "1") (pinfunction "1_1") (pintype "passive"))
      (node (ref "R27") (pin "1") (pinfunction "1_1") (pintype "passive"))
      (node (ref "R28") (pin "1") (pinfunction "1_1") (pintype "passive"))
      (node (ref "R29") (pin "1") (pinfunction "1_1") (pintype "passive"))
      (node (ref "R3") (pin "2") (pinfunction "2_2") (pintype "passive"))
      (node (ref "R32") (pin "1") (pinfunction "1_1") (pintype "passive"))
      (node (ref "R5") (pin "2") (pinfunction "2_2") (pintype "passive"))
      (node (ref "R7") (pin "1") (pinfunction "1_1") (pintype "passive"))
      (node (ref "R8") (pin "1") (pinfunction "1_1") (pintype "passive"))
      (node (ref "R9") (pin "1") (pinfunction "1_1") (pintype "passive"))
      (node (ref "SW1") (pin "2") (pinfunction "2_2") (pintype "passive"))
      (node (ref "SW2") (pin "2") (pinfunction "2_2") (pintype "passive"))
      (node (ref "SW4") (pin "3") (pinfunction "3_3") (pintype "passive"))
      (node (ref "U1") (pin "15") (pinfunction "GND_15") (pintype "power_in"))
      (node (ref "U1") (pin "16") (pinfunction "PMODE_16") (pintype "input"))
      (node (ref "U1") (pin "17") (pinfunction "Thermal_Pad_17") (pintype "power_in"))
      (node (ref "U1") (pin "9") (pinfunction "PGND_9") (pintype "power_in"))
      (node (ref "U2") (pin "2") (pinfunction "GND_2") (pintype "power_in"))
      (node (ref "U3") (pin "15") (pinfunction "GND_15") (pintype "power_in"))
      (node (ref "U3") (pin "16") (pinfunction "PMODE_16") (pintype "input"))
      (node (ref "U3") (pin "17") (pinfunction "Thermal_Pad_17") (pintype "power_in"))
      (node (ref "U3") (pin "9") (pinfunction "PGND_9") (pintype "power_in"))
      (node (ref "U4") (pin "23") (pinfunction "VSS_23") (pintype "power_in"))
      (node (ref "U4") (pin "35") (pinfunction "VSS_35") (pintype "power_in"))
      (node (ref "U4") (pin "47") (pinfunction "VSS_47") (pintype "power_in"))
      (node (ref "U4") (pin "49") (pinfunction "EP_49") (pintype "power_in"))
      (node (ref "U4") (pin "8") (pinfunction "VSSA_8") (pintype "power_in"))
      (node (ref "U5") (pin "3") (pinfunction "VSS_3") (pintype "power_in"))
      (node (ref "U6") (pin "1") (pinfunction "Adjust_1") (pintype "passive"))
      (node (ref "U9") (pin "10") (pinfunction "RES_10") (pintype "passive"))
      (node (ref "U9") (pin "12") (pinfunction "GND_12") (pintype "power_in"))
      (node (ref "U9") (pin "5") (pinfunction "GND_5") (pintype "power_in"))
      (node (ref "X322525MOB4SI") (pin "2") (pinfunction "2_2") (pintype "passive"))
      (node (ref "X322525MOB4SI") (pin "4") (pinfunction "4_4") (pintype "passive"))
    )
    (net (code "39") (name "Net-(D1-C)") (class "Default")
      (node (ref "C29") (pin "2") (pinfunction "2_2") (pintype "passive"))
      (node (ref "D1") (pin "1") (pinfunction "C_1") (pintype "passive"))
      (node (ref "Q1") (pin "3") (pinfunction "D_3") (pintype "passive"))
      (node (ref "R30") (pin "1") (pinfunction "1_1") (pintype "passive"))
      (node (ref "U2") (pin "1") (pinfunction "VIN_1") (pintype "power_in"))
    )
    (net (code "40") (name "Net-(D6-C)") (class "Default")
      (node (ref "D6") (pin "1") (pinfunction "C_1") (pintype "passive"))
      (node (ref "R11") (pin "2") (pinfunction "2_2") (pintype "passive"))
    )
    (net (code "41") (name "Net-(D8-C)") (class "Default")
      (node (ref "D8") (pin "1") (pinfunction "C_1") (pintype "passive"))
      (node (ref "R20") (pin "2") (pinfunction "2_2") (pintype "passive"))
    )
    (net (code "42") (name "Net-(D11-A)") (class "Default")
      (node (ref "D11") (pin "2") (pinfunction "A_2") (pintype "passive"))
      (node (ref "D7") (pin "1") (pinfunction "C_1") (pintype "passive"))
    )
    (net (code "43") (name "Net-(D11-C)") (class "Default")
      (node (ref "D11") (pin "1") (pinfunction "C_1") (pintype "passive"))
      (node (ref "R21") (pin "1") (pinfunction "1_1") (pintype "passive"))
      (node (ref "R22") (pin "1") (pinfunction "1_1") (pintype "passive"))
    )
    (net (code "44") (name "Net-(D12-A)") (class "Default")
      (node (ref "D12") (pin "1") (pinfunction "A_1") (pintype "passive"))
      (node (ref "R31") (pin "1") (pinfunction "1_1") (pintype "passive"))
    )
    (net (code "45") (name "Net-(J3-CC1)") (class "Default")
      (node (ref "J3") (pin "3") (pinfunction "CC1_3") (pintype "passive"))
      (node (ref "R15") (pin "2") (pinfunction "2_2") (pintype "passive"))
    )
    (net (code "46") (name "Net-(J3-CC2)") (class "Default")
      (node (ref "J3") (pin "9") (pinfunction "CC2_9") (pintype "passive"))
      (node (ref "R32") (pin "2") (pinfunction "2_2") (pintype "passive"))
    )
    (net (code "47") (name "Net-(Q2-DRAIN)") (class "Default")
      (node (ref "Q2") (pin "3") (pinfunction "DRAIN_3") (pintype "passive"))
      (node (ref "R11") (pin "1") (pinfunction "1_1") (pintype "passive"))
    )
    (net (code "48") (name "Net-(Q3-DRAIN)") (class "Default")
      (node (ref "Q3") (pin "3") (pinfunction "DRAIN_3") (pintype "passive"))
      (node (ref "R20") (pin "1") (pinfunction "1_1") (pintype "passive"))
    )
    (net (code "49") (name "Net-(Q4-DRAIN)") (class "Default")
      (node (ref "Q4") (pin "3") (pinfunction "DRAIN_3") (pintype "passive"))
      (node (ref "R21") (pin "2") (pinfunction "2_2") (pintype "passive"))
      (node (ref "R22") (pin "2") (pinfunction "2_2") (pintype "passive"))
    )
    (net (code "50") (name "Net-(R17-Pad1)") (class "Default")
      (node (ref "R17") (pin "1") (pinfunction "1_1") (pintype "passive"))
      (node (ref "SW4") (pin "4") (pinfunction "4_4") (pintype "passive"))
    )
    (net (code "51") (name "Net-(U1-CPH)") (class "Default")
      (node (ref "C1") (pin "2") (pinfunction "2_2") (pintype "passive"))
      (node (ref "U1") (pin "13") (pinfunction "CPH_13") (pintype "power_in"))
    )
    (net (code "52") (name "Net-(U1-CPL)") (class "Default")
      (node (ref "C1") (pin "1") (pinfunction "1_1") (pintype "passive"))
      (node (ref "U1") (pin "14") (pinfunction "CPL_14") (pintype "power_in"))
    )
    (net (code "53") (name "Net-(U1-IMODE)") (class "Default")
      (node (ref "R2") (pin "2") (pinfunction "2_2") (pintype "passive"))
      (node (ref "U1") (pin "7") (pinfunction "IMODE_7") (pintype "input"))
    )
    (net (code "54") (name "Net-(U1-IPROPI)") (class "Default")
      (node (ref "R1") (pin "2") (pinfunction "2_2") (pintype "passive"))
      (node (ref "U1") (pin "6") (pinfunction "IPROPI_6") (pintype "output"))
    )
    (net (code "55") (name "Net-(U1-VREF)") (class "Default")
      (node (ref "R3") (pin "1") (pinfunction "1_1") (pintype "passive"))
      (node (ref "R4") (pin "2") (pinfunction "2_2") (pintype "passive"))
      (node (ref "U1") (pin "5") (pinfunction "VREF_5") (pintype "power_in"))
    )
    (net (code "56") (name "Net-(U1-~{FAULT})") (class "Default")
      (node (ref "R12") (pin "2") (pinfunction "2_2") (pintype "passive"))
      (node (ref "U1") (pin "4") (pinfunction "~{FAULT}_4") (pintype "output"))
    )
    (net (code "57") (name "Net-(U1-~{SLEEP})") (class "Default")
      (node (ref "R4") (pin "1") (pinfunction "1_1") (pintype "passive"))
      (node (ref "U1") (pin "3") (pinfunction "~{SLEEP}_3") (pintype "input"))
    )
    (net (code "58") (name "Net-(U2-EN)") (class "Default")
      (node (ref "R30") (pin "2") (pinfunction "2_2") (pintype "passive"))
      (node (ref "U2") (pin "3") (pinfunction "EN_3") (pintype "input"))
    )
    (net (code "59") (name "Net-(U3-CPH)") (class "Default")
      (node (ref "C7") (pin "2") (pinfunction "2_2") (pintype "passive"))
      (node (ref "U3") (pin "13") (pinfunction "CPH_13") (pintype "power_in"))
    )
    (net (code "60") (name "Net-(U3-CPL)") (class "Default")
      (node (ref "C7") (pin "1") (pinfunction "1_1") (pintype "passive"))
      (node (ref "U3") (pin "14") (pinfunction "CPL_14") (pintype "power_in"))
    )
    (net (code "61") (name "Net-(U3-IMODE)") (class "Default")
      (node (ref "R8") (pin "2") (pinfunction "2_2") (pintype "passive"))
      (node (ref "U3") (pin "7") (pinfunction "IMODE_7") (pintype "input"))
    )
    (net (code "62") (name "Net-(U3-IPROPI)") (class "Default")
      (node (ref "R7") (pin "2") (pinfunction "2_2") (pintype "passive"))
      (node (ref "U3") (pin "6") (pinfunction "IPROPI_6") (pintype "output"))
    )
    (net (code "63") (name "Net-(U3-VREF)") (class "Default")
      (node (ref "R5") (pin "1") (pinfunction "1_1") (pintype "passive"))
      (node (ref "R6") (pin "2") (pinfunction "2_2") (pintype "passive"))
      (node (ref "U3") (pin "5") (pinfunction "VREF_5") (pintype "power_in"))
    )
    (net (code "64") (name "Net-(U3-~{FAULT})") (class "Default")
      (node (ref "R13") (pin "2") (pinfunction "2_2") (pintype "passive"))
      (node (ref "U3") (pin "4") (pinfunction "~{FAULT}_4") (pintype "output"))
    )
    (net (code "65") (name "Net-(U3-~{SLEEP})") (class "Default")
      (node (ref "R6") (pin "1") (pinfunction "1_1") (pintype "passive"))
      (node (ref "U3") (pin "3") (pinfunction "~{SLEEP}_3") (pintype "input"))
    )
    (net (code "66") (name "Net-(U4-BOOT0)") (class "Default")
      (node (ref "R17") (pin "2") (pinfunction "2_2") (pintype "passive"))
      (node (ref "U4") (pin "44") (pinfunction "BOOT0_44") (pintype "input"))
    )
    (net (code "67") (name "Net-(U4-VCAP1)") (class "Default")
      (node (ref "C9") (pin "2") (pinfunction "2_2") (pintype "passive"))
      (node (ref "U4") (pin "22") (pinfunction "VCAP1_22") (pintype "passive"))
    )
    (net (code "68") (name "Net-(U9-CS)") (class "Default")
      (node (ref "R19") (pin "2") (pinfunction "2_2") (pintype "passive"))
      (node (ref "U9") (pin "8") (pinfunction "CS_8") (pintype "input"))
    )
    (net (code "69") (name "Net-(U9-SDO{slash}SA0)") (class "Default")
      (node (ref "R18") (pin "2") (pinfunction "2_2") (pintype "passive"))
      (node (ref "U9") (pin "7") (pinfunction "SDO/SA0_7") (pintype "bidirectional"))
    )
    (net (code "70") (name "VBAT") (class "Default")
      (node (ref "C2") (pin "1") (pinfunction "1_1") (pintype "passive"))
      (node (ref "C3") (pin "1") (pinfunction "1_1") (pintype "passive"))
      (node (ref "C30") (pin "1") (pinfunction "1_1") (pintype "passive"))
      (node (ref "C31") (pin "1") (pinfunction "1_1") (pintype "passive"))
      (node (ref "C4") (pin "1") (pinfunction "1_1") (pintype "passive"))
      (node (ref "C5") (pin "1") (pinfunction "1_1") (pintype "passive"))
      (node (ref "C6") (pin "1") (pinfunction "1_1") (pintype "passive"))
      (node (ref "C8") (pin "1") (pinfunction "1_1") (pintype "passive"))
      (node (ref "J4") (pin "1") (pinfunction "1_1") (pintype "passive"))
      (node (ref "U1") (pin "11") (pinfunction "VM_11") (pintype "power_in"))
      (node (ref "U3") (pin "11") (pinfunction "VM_11") (pintype "power_in"))
      (node (ref "U6") (pin "3") (pinfunction "VIN_3") (pintype "power_in"))
    )
    (net (code "71") (name "VBUS") (class "Default")
      (node (ref "D1") (pin "2") (pinfunction "A_2") (pintype "passive"))
      (node (ref "J3") (pin "11") (pinfunction "VBUS_11") (pintype "power_in"))
      (node (ref "J3") (pin "2") (pinfunction "VBUS_2") (pintype "power_in"))
      (node (ref "Q1") (pin "1") (pinfunction "G_1") (pintype "passive"))
      (node (ref "R9") (pin "2") (pinfunction "2_2") (pintype "passive"))
    )
    (net (code "72") (name "unconnected-(J3-SBU1-Pad10)") (class "Default")
      (node (ref "J3") (pin "10") (pinfunction "SBU1_10") (pintype "passive+no_connect"))
    )
    (net (code "73") (name "unconnected-(J3-SBU2-Pad4)") (class "Default")
      (node (ref "J3") (pin "4") (pinfunction "SBU2_4") (pintype "passive+no_connect"))
    )
    (net (code "74") (name "unconnected-(SW1-Pad1)") (class "Default")
      (node (ref "SW1") (pin "1") (pinfunction "1_1") (pintype "passive"))
    )
    (net (code "75") (name "unconnected-(SW1-Pad3)") (class "Default")
      (node (ref "SW1") (pin "3") (pinfunction "3_3") (pintype "passive"))
    )
    (net (code "76") (name "unconnected-(SW2-Pad1)") (class "Default")
      (node (ref "SW2") (pin "1") (pinfunction "1_1") (pintype "passive"))
    )
    (net (code "77") (name "unconnected-(SW2-Pad3)") (class "Default")
      (node (ref "SW2") (pin "3") (pinfunction "3_3") (pintype "passive"))
    )
    (net (code "78") (name "unconnected-(SW4-Pad1)") (class "Default")
      (node (ref "SW4") (pin "1") (pinfunction "1_1") (pintype "passive"))
    )
    (net (code "79") (name "unconnected-(U2-NC-Pad4)") (class "Default")
      (node (ref "U2") (pin "4") (pinfunction "NC_4") (pintype "passive+no_connect"))
    )
    (net (code "80") (name "unconnected-(U4-PA0-WKUP-Pad10)") (class "Default")
      (node (ref "U4") (pin "10") (pinfunction "PA0-WKUP_10") (pintype "bidirectional"))
    )
    (net (code "81") (name "unconnected-(U4-PA10-Pad31)") (class "Default")
      (node (ref "U4") (pin "31") (pinfunction "PA10_31") (pintype "bidirectional"))
    )
    (net (code "82") (name "unconnected-(U4-PA15-Pad38)") (class "Default")
      (node (ref "U4") (pin "38") (pinfunction "PA15_38") (pintype "bidirectional+no_connect"))
    )
    (net (code "83") (name "unconnected-(U4-PB0-Pad18)") (class "Default")
      (node (ref "U4") (pin "18") (pinfunction "PB0_18") (pintype "bidirectional"))
    )
    (net (code "84") (name "unconnected-(U4-PB4-Pad40)") (class "Default")
      (node (ref "U4") (pin "40") (pinfunction "PB4_40") (pintype "bidirectional+no_connect"))
    )
    (net (code "85") (name "unconnected-(U4-PB5-Pad41)") (class "Default")
      (node (ref "U4") (pin "41") (pinfunction "PB5_41") (pintype "bidirectional+no_connect"))
    )
    (net (code "86") (name "unconnected-(U4-PC13-ANTI_TAMP-Pad2)") (class "Default")
      (node (ref "U4") (pin "2") (pinfunction "PC13-ANTI_TAMP_2") (pintype "bidirectional+no_connect"))
    )
    (net (code "87") (name "unconnected-(U4-PC14-OSC32_IN-Pad3)") (class "Default")
      (node (ref "U4") (pin "3") (pinfunction "PC14-OSC32_IN_3") (pintype "bidirectional+no_connect"))
    )
    (net (code "88") (name "unconnected-(U4-PC15-OSC32_OUT-Pad4)") (class "Default")
      (node (ref "U4") (pin "4") (pinfunction "PC15-OSC32_OUT_4") (pintype "bidirectional+no_connect"))
    )
    (net (code "89") (name "unconnected-(U5-DOUT-Pad2)") (class "Default")
      (node (ref "U5") (pin "2") (pinfunction "DOUT_2") (pintype "output+no_connect"))
    )
    (net (code "90") (name "unconnected-(U9-ADC1-Pad16)") (class "Default")
      (node (ref "U9") (pin "16") (pinfunction "ADC1_16") (pintype "passive+no_connect"))
    )
    (net (code "91") (name "unconnected-(U9-ADC2-Pad15)") (class "Default")
      (node (ref "U9") (pin "15") (pinfunction "ADC2_15") (pintype "passive+no_connect"))
    )
    (net (code "92") (name "unconnected-(U9-ADC3-Pad13)") (class "Default")
      (node (ref "U9") (pin "13") (pinfunction "ADC3_13") (pintype "passive+no_connect"))
    )
    (net (code "93") (name "unconnected-(U9-INT2-Pad9)") (class "Default")
      (node (ref "U9") (pin "9") (pinfunction "INT2_9") (pintype "output+no_connect"))
    )
    (net (code "94") (name "unconnected-(U9-NC-Pad2)") (class "Default")
      (node (ref "U9") (pin "2") (pinfunction "NC_2") (pintype "passive+no_connect"))
    )
    (net (code "95") (name "unconnected-(U9-NC-Pad3)") (class "Default")
      (node (ref "U9") (pin "3") (pinfunction "NC_3") (pintype "passive+no_connect"))
    )
  )
)
